# Node_MCU_Power_Shield.net
KiCad netlist of a schematic drawn in Altium Designer
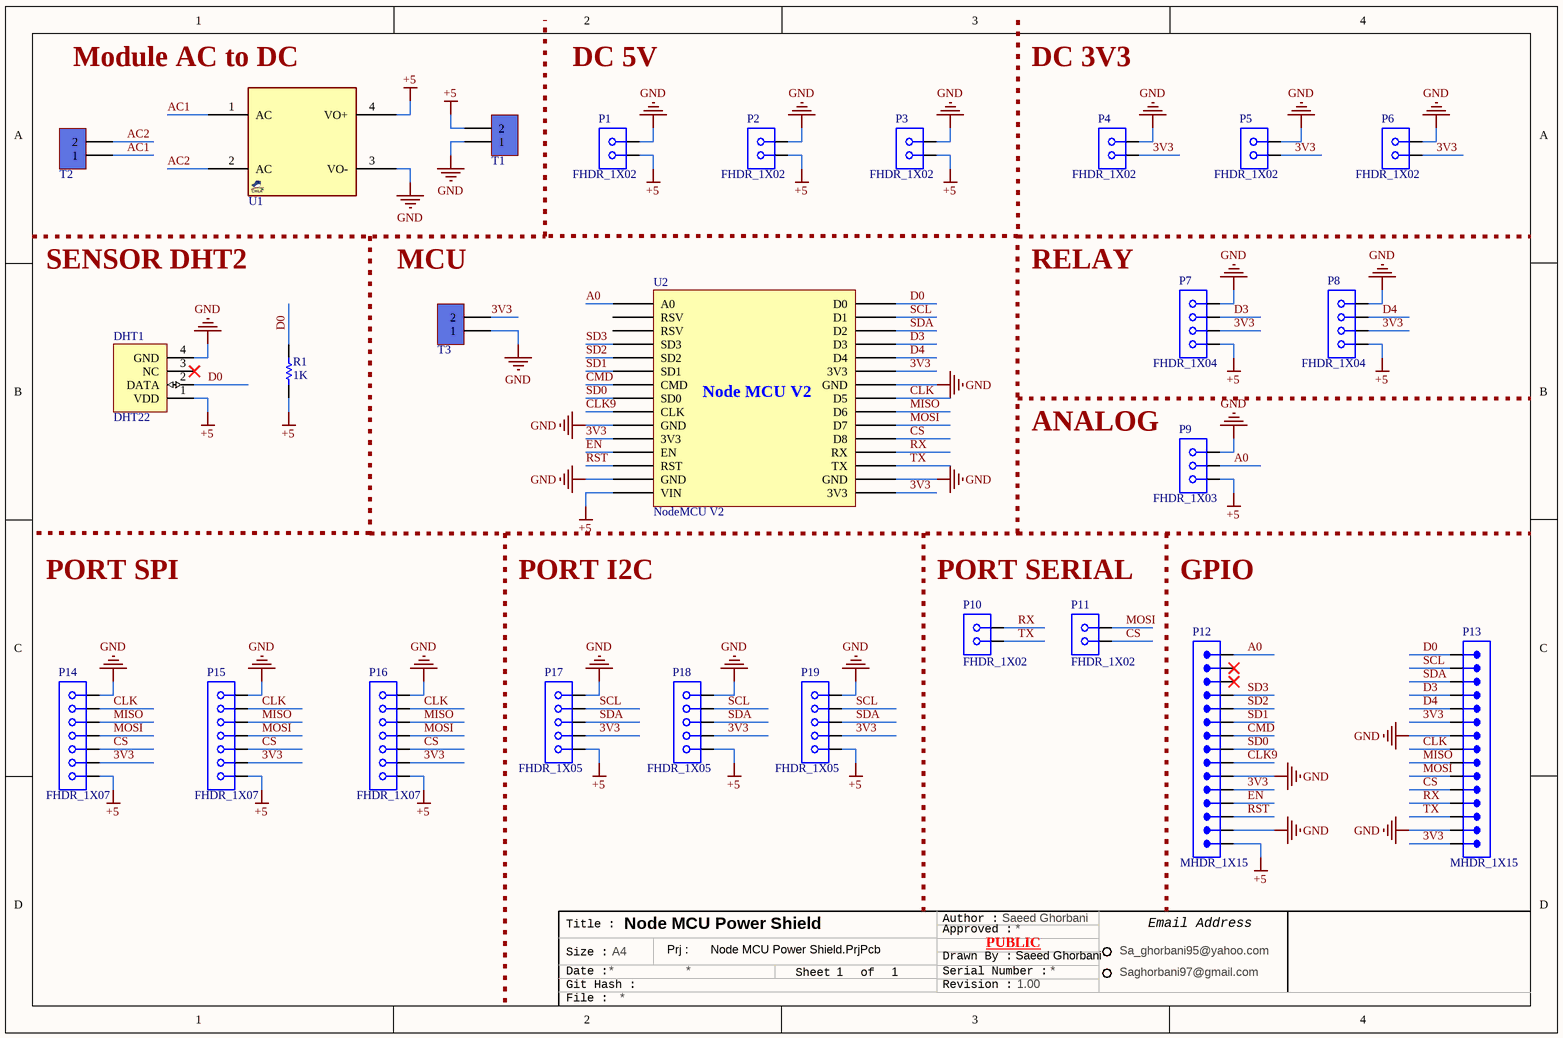
[diagram p0: Node MCU Power Shield.SchDoc]

(export (version "E")
  (design (tool "Eeschema 10.0.6"))
  (components
    (comp (ref "DHT1")
      (value "DHT22")
      (footprint "DHT22_THD")
      (description "Digital Humidity & Temprature Sensor")
      (libsource (lib "Altium") (part "DHT22"))
    )
    (comp (ref "P1")
      (value "FHDR_1X02")
      (footprint "FHDR1X02-254P")
      (description "Female Header 1X02")
      (libsource (lib "SJ Sockets & Connectors") (part "FHDR_1X02"))
    )
    (comp (ref "P2")
      (value "FHDR_1X02")
      (footprint "FHDR1X02-254P")
      (description "Female Header 1X02")
      (libsource (lib "SJ Sockets & Connectors") (part "FHDR_1X02"))
    )
    (comp (ref "P3")
      (value "FHDR_1X02")
      (footprint "FHDR1X02-254P")
      (description "Female Header 1X02")
      (libsource (lib "SJ Sockets & Connectors") (part "FHDR_1X02"))
    )
    (comp (ref "P4")
      (value "FHDR_1X02")
      (footprint "FHDR1X02-254P")
      (description "Female Header 1X02")
      (libsource (lib "SJ Sockets & Connectors") (part "FHDR_1X02"))
    )
    (comp (ref "P5")
      (value "FHDR_1X02")
      (footprint "FHDR1X02-254P")
      (description "Female Header 1X02")
      (libsource (lib "SJ Sockets & Connectors") (part "FHDR_1X02"))
    )
    (comp (ref "P6")
      (value "FHDR_1X02")
      (footprint "FHDR1X02-254P")
      (description "Female Header 1X02")
      (libsource (lib "SJ Sockets & Connectors") (part "FHDR_1X02"))
    )
    (comp (ref "P7")
      (value "FHDR_1X04")
      (footprint "FHDR1X04-254P")
      (description "Female Header 1X04")
      (libsource (lib "SJ Sockets & Connectors") (part "FHDR_1X04"))
    )
    (comp (ref "P8")
      (value "FHDR_1X04")
      (footprint "FHDR1X04-254P")
      (description "Female Header 1X04")
      (libsource (lib "SJ Sockets & Connectors") (part "FHDR_1X04"))
    )
    (comp (ref "P9")
      (value "FHDR_1X03")
      (footprint "FHDR1X03-254P")
      (description "Female Header 1X03")
      (libsource (lib "SJ Sockets & Connectors") (part "FHDR_1X03"))
    )
    (comp (ref "P10")
      (value "FHDR_1X02")
      (footprint "FHDR1X02-254P")
      (description "Female Header 1X02")
      (libsource (lib "SJ Sockets & Connectors") (part "FHDR_1X02"))
    )
    (comp (ref "P11")
      (value "FHDR_1X02")
      (footprint "FHDR1X02-254P")
      (description "Female Header 1X02")
      (libsource (lib "SJ Sockets & Connectors") (part "FHDR_1X02"))
    )
    (comp (ref "P12")
      (value "MHDR_1X15")
      (footprint "MHDR1X15-254P")
      (description "Male Header 1X15")
      (libsource (lib "SJ Sockets & Connectors") (part "MHDR_1X15"))
    )
    (comp (ref "P13")
      (value "MHDR_1X15")
      (footprint "MHDR1X15-254P")
      (description "Male Header 1X15")
      (libsource (lib "SJ Sockets & Connectors") (part "MHDR_1X15"))
    )
    (comp (ref "P14")
      (value "FHDR_1X07")
      (footprint "FHDR1X07-254P")
      (description "Female Header 1X07")
      (libsource (lib "SJ Sockets & Connectors") (part "FHDR_1X07"))
    )
    (comp (ref "P15")
      (value "FHDR_1X07")
      (footprint "FHDR1X07-254P")
      (description "Female Header 1X07")
      (libsource (lib "SJ Sockets & Connectors") (part "FHDR_1X07"))
    )
    (comp (ref "P16")
      (value "FHDR_1X07")
      (footprint "FHDR1X07-254P")
      (description "Female Header 1X07")
      (libsource (lib "SJ Sockets & Connectors") (part "FHDR_1X07"))
    )
    (comp (ref "P17")
      (value "FHDR_1X05")
      (footprint "FHDR1X05-254P")
      (description "Female Header 1X05")
      (libsource (lib "SJ Sockets & Connectors") (part "FHDR_1X05"))
    )
    (comp (ref "P18")
      (value "FHDR_1X05")
      (footprint "FHDR1X05-254P")
      (description "Female Header 1X05")
      (libsource (lib "SJ Sockets & Connectors") (part "FHDR_1X05"))
    )
    (comp (ref "P19")
      (value "FHDR_1X05")
      (footprint "FHDR1X05-254P")
      (description "Female Header 1X05")
      (libsource (lib "SJ Sockets & Connectors") (part "FHDR_1X05"))
    )
    (comp (ref "R1")
      (value "1K")
      (footprint "RES-(1/8)")
      (description "TOTAL DIP RESISTOR PACK")
      (fields (field (name "DESIGNER") "Ali Hafizi"))
      (libsource (lib "Altium") (part "RES DIP PACKAGE"))
    )
    (comp (ref "T1")
      (value "KF301_Terminal")
      (footprint "KF301 2PIN")
      (description "Terminal 2 Pin 250VAC 16A")
      (fields (field (name "DESIGNER") "Abbas Basereh"))
      (libsource (lib "") (part "KF301-2Pin_Terminal_1"))
    )
    (comp (ref "T2")
      (value "KF301_Terminal")
      (footprint "KF301 2PIN")
      (description "Terminal 2 Pin 250VAC 16A")
      (fields (field (name "DESIGNER") "Abbas Basereh"))
      (libsource (lib "Altium") (part "KF301-2Pin_Terminal"))
    )
    (comp (ref "T3")
      (value "KF301_Terminal")
      (footprint "KF301 2PIN")
      (description "Terminal 2 Pin 250VAC 16A")
      (fields (field (name "DESIGNER") "Abbas Basereh"))
      (libsource (lib "Altium") (part "KF301-2Pin_Terminal"))
    )
    (comp (ref "U1")
      (value "HLK-5M03")
      (footprint "HLK5M_4_38X23")
      (description "AC/DC CONVERTER")
      (fields (field (name "MANF") "HI-LINK"))
      (libsource (lib "module_ac2dc") (part "HLK-5M03"))
    )
    (comp (ref "U2")
      (value "NodeMCU V2")
      (footprint "NodeMCU V1.0 ESP-12E")
      (libsource (lib "NodeMCU") (part "NodeMCU V2"))
    )
  )
  (nets
    (net (code "1") (name "+5") (class "Default")
      (node (ref "DHT1") (pin "1") (pinfunction "VDD_1") (pintype "power_in"))
      (node (ref "P1") (pin "1") (pinfunction "1_1") (pintype "passive"))
      (node (ref "P12") (pin "1") (pinfunction "1_1") (pintype "passive"))
      (node (ref "P14") (pin "1") (pinfunction "1_1") (pintype "passive"))
      (node (ref "P15") (pin "1") (pinfunction "1_1") (pintype "passive"))
      (node (ref "P16") (pin "1") (pinfunction "1_1") (pintype "passive"))
      (node (ref "P17") (pin "1") (pinfunction "1_1") (pintype "passive"))
      (node (ref "P18") (pin "1") (pinfunction "1_1") (pintype "passive"))
      (node (ref "P19") (pin "1") (pinfunction "1_1") (pintype "passive"))
      (node (ref "P2") (pin "1") (pinfunction "1_1") (pintype "passive"))
      (node (ref "P3") (pin "1") (pinfunction "1_1") (pintype "passive"))
      (node (ref "P7") (pin "1") (pinfunction "1_1") (pintype "passive"))
      (node (ref "P8") (pin "1") (pinfunction "1_1") (pintype "passive"))
      (node (ref "P9") (pin "1") (pinfunction "1_1") (pintype "passive"))
      (node (ref "R1") (pin "1") (pinfunction "1_1") (pintype "passive"))
      (node (ref "T1") (pin "2") (pinfunction "2_2") (pintype "passive"))
      (node (ref "U1") (pin "4") (pinfunction "VO+_4") (pintype "power_in"))
      (node (ref "U2") (pin "15") (pinfunction "VIN_15") (pintype "passive"))
    )
    (net (code "2") (name "/3V3") (class "Default")
      (node (ref "P12") (pin "5") (pinfunction "5_5") (pintype "passive"))
      (node (ref "P13") (pin "15") (pinfunction "15_15") (pintype "passive"))
      (node (ref "P13") (pin "6") (pinfunction "6_6") (pintype "passive"))
      (node (ref "P14") (pin "2") (pinfunction "2_2") (pintype "passive"))
      (node (ref "P15") (pin "2") (pinfunction "2_2") (pintype "passive"))
      (node (ref "P16") (pin "2") (pinfunction "2_2") (pintype "passive"))
      (node (ref "P17") (pin "2") (pinfunction "2_2") (pintype "passive"))
      (node (ref "P18") (pin "2") (pinfunction "2_2") (pintype "passive"))
      (node (ref "P19") (pin "2") (pinfunction "2_2") (pintype "passive"))
      (node (ref "P4") (pin "1") (pinfunction "1_1") (pintype "passive"))
      (node (ref "P5") (pin "1") (pinfunction "1_1") (pintype "passive"))
      (node (ref "P6") (pin "1") (pinfunction "1_1") (pintype "passive"))
      (node (ref "P7") (pin "2") (pinfunction "2_2") (pintype "passive"))
      (node (ref "P8") (pin "2") (pinfunction "2_2") (pintype "passive"))
      (node (ref "T3") (pin "2") (pinfunction "2_2") (pintype "passive"))
      (node (ref "U2") (pin "11") (pinfunction "3V3_11") (pintype "passive"))
      (node (ref "U2") (pin "16") (pinfunction "3V3_16") (pintype "passive"))
      (node (ref "U2") (pin "25") (pinfunction "3V3_25") (pintype "passive"))
    )
    (net (code "3") (name "/A0") (class "Default")
      (node (ref "P12") (pin "15") (pinfunction "15_15") (pintype "passive"))
      (node (ref "P9") (pin "2") (pinfunction "2_2") (pintype "passive"))
      (node (ref "U2") (pin "1") (pinfunction "A0_1") (pintype "passive"))
    )
    (net (code "4") (name "/AC1") (class "Default")
      (node (ref "T2") (pin "1") (pinfunction "1_1") (pintype "passive"))
      (node (ref "U1") (pin "1") (pinfunction "AC_1") (pintype "power_in"))
    )
    (net (code "5") (name "/AC2") (class "Default")
      (node (ref "T2") (pin "2") (pinfunction "2_2") (pintype "passive"))
      (node (ref "U1") (pin "2") (pinfunction "AC_2") (pintype "power_in"))
    )
    (net (code "6") (name "/CLK") (class "Default")
      (node (ref "P13") (pin "8") (pinfunction "8_8") (pintype "passive"))
      (node (ref "P14") (pin "6") (pinfunction "6_6") (pintype "passive"))
      (node (ref "P15") (pin "6") (pinfunction "6_6") (pintype "passive"))
      (node (ref "P16") (pin "6") (pinfunction "6_6") (pintype "passive"))
      (node (ref "U2") (pin "23") (pinfunction "D5_23") (pintype "passive"))
    )
    (net (code "7") (name "/CLK9") (class "Default")
      (node (ref "P12") (pin "7") (pinfunction "7_7") (pintype "passive"))
      (node (ref "U2") (pin "9") (pinfunction "CLK_9") (pintype "passive"))
    )
    (net (code "8") (name "/CMD") (class "Default")
      (node (ref "P12") (pin "9") (pinfunction "9_9") (pintype "passive"))
      (node (ref "U2") (pin "7") (pinfunction "CMD_7") (pintype "passive"))
    )
    (net (code "9") (name "/CS") (class "Default")
      (node (ref "P11") (pin "1") (pinfunction "1_1") (pintype "passive"))
      (node (ref "P13") (pin "11") (pinfunction "11_11") (pintype "passive"))
      (node (ref "P14") (pin "3") (pinfunction "3_3") (pintype "passive"))
      (node (ref "P15") (pin "3") (pinfunction "3_3") (pintype "passive"))
      (node (ref "P16") (pin "3") (pinfunction "3_3") (pintype "passive"))
      (node (ref "U2") (pin "20") (pinfunction "D8_20") (pintype "passive"))
    )
    (net (code "10") (name "/D0") (class "Default")
      (node (ref "DHT1") (pin "2") (pinfunction "DATA_2") (pintype "bidirectional"))
      (node (ref "P13") (pin "1") (pinfunction "1_1") (pintype "passive"))
      (node (ref "R1") (pin "2") (pinfunction "2_2") (pintype "passive"))
      (node (ref "U2") (pin "30") (pinfunction "D0_30") (pintype "passive"))
    )
    (net (code "11") (name "/D3") (class "Default")
      (node (ref "P13") (pin "4") (pinfunction "4_4") (pintype "passive"))
      (node (ref "P7") (pin "3") (pinfunction "3_3") (pintype "passive"))
      (node (ref "U2") (pin "27") (pinfunction "D3_27") (pintype "passive"))
    )
    (net (code "12") (name "/D4") (class "Default")
      (node (ref "P13") (pin "5") (pinfunction "5_5") (pintype "passive"))
      (node (ref "P8") (pin "3") (pinfunction "3_3") (pintype "passive"))
      (node (ref "U2") (pin "26") (pinfunction "D4_26") (pintype "passive"))
    )
    (net (code "13") (name "/EN") (class "Default")
      (node (ref "P12") (pin "4") (pinfunction "4_4") (pintype "passive"))
      (node (ref "U2") (pin "12") (pinfunction "EN_12") (pintype "passive"))
    )
    (net (code "14") (name "/MISO") (class "Default")
      (node (ref "P13") (pin "9") (pinfunction "9_9") (pintype "passive"))
      (node (ref "P14") (pin "5") (pinfunction "5_5") (pintype "passive"))
      (node (ref "P15") (pin "5") (pinfunction "5_5") (pintype "passive"))
      (node (ref "P16") (pin "5") (pinfunction "5_5") (pintype "passive"))
      (node (ref "U2") (pin "22") (pinfunction "D6_22") (pintype "passive"))
    )
    (net (code "15") (name "/MOSI") (class "Default")
      (node (ref "P11") (pin "2") (pinfunction "2_2") (pintype "passive"))
      (node (ref "P13") (pin "10") (pinfunction "10_10") (pintype "passive"))
      (node (ref "P14") (pin "4") (pinfunction "4_4") (pintype "passive"))
      (node (ref "P15") (pin "4") (pinfunction "4_4") (pintype "passive"))
      (node (ref "P16") (pin "4") (pinfunction "4_4") (pintype "passive"))
      (node (ref "U2") (pin "21") (pinfunction "D7_21") (pintype "passive"))
    )
    (net (code "16") (name "/RST") (class "Default")
      (node (ref "P12") (pin "3") (pinfunction "3_3") (pintype "passive"))
      (node (ref "U2") (pin "13") (pinfunction "RST_13") (pintype "passive"))
    )
    (net (code "17") (name "/RX") (class "Default")
      (node (ref "P10") (pin "2") (pinfunction "2_2") (pintype "passive"))
      (node (ref "P13") (pin "12") (pinfunction "12_12") (pintype "passive"))
      (node (ref "U2") (pin "19") (pinfunction "RX_19") (pintype "passive"))
    )
    (net (code "18") (name "/SCL") (class "Default")
      (node (ref "P13") (pin "2") (pinfunction "2_2") (pintype "passive"))
      (node (ref "P17") (pin "4") (pinfunction "4_4") (pintype "passive"))
      (node (ref "P18") (pin "4") (pinfunction "4_4") (pintype "passive"))
      (node (ref "P19") (pin "4") (pinfunction "4_4") (pintype "passive"))
      (node (ref "U2") (pin "29") (pinfunction "D1_29") (pintype "passive"))
    )
    (net (code "19") (name "/SD0") (class "Default")
      (node (ref "P12") (pin "8") (pinfunction "8_8") (pintype "passive"))
      (node (ref "U2") (pin "8") (pinfunction "SD0_8") (pintype "passive"))
    )
    (net (code "20") (name "/SD1") (class "Default")
      (node (ref "P12") (pin "10") (pinfunction "10_10") (pintype "passive"))
      (node (ref "U2") (pin "6") (pinfunction "SD1_6") (pintype "passive"))
    )
    (net (code "21") (name "/SD2") (class "Default")
      (node (ref "P12") (pin "11") (pinfunction "11_11") (pintype "passive"))
      (node (ref "U2") (pin "5") (pinfunction "SD2_5") (pintype "passive"))
    )
    (net (code "22") (name "/SD3") (class "Default")
      (node (ref "P12") (pin "12") (pinfunction "12_12") (pintype "passive"))
      (node (ref "U2") (pin "4") (pinfunction "SD3_4") (pintype "passive"))
    )
    (net (code "23") (name "/SDA") (class "Default")
      (node (ref "P13") (pin "3") (pinfunction "3_3") (pintype "passive"))
      (node (ref "P17") (pin "3") (pinfunction "3_3") (pintype "passive"))
      (node (ref "P18") (pin "3") (pinfunction "3_3") (pintype "passive"))
      (node (ref "P19") (pin "3") (pinfunction "3_3") (pintype "passive"))
      (node (ref "U2") (pin "28") (pinfunction "D2_28") (pintype "passive"))
    )
    (net (code "24") (name "/TX") (class "Default")
      (node (ref "P10") (pin "1") (pinfunction "1_1") (pintype "passive"))
      (node (ref "P13") (pin "13") (pinfunction "13_13") (pintype "passive"))
      (node (ref "U2") (pin "18") (pinfunction "TX_18") (pintype "passive"))
    )
    (net (code "25") (name "GND") (class "Default")
      (node (ref "DHT1") (pin "4") (pinfunction "GND_4") (pintype "power_in"))
      (node (ref "P1") (pin "2") (pinfunction "2_2") (pintype "passive"))
      (node (ref "P12") (pin "2") (pinfunction "2_2") (pintype "passive"))
      (node (ref "P12") (pin "6") (pinfunction "6_6") (pintype "passive"))
      (node (ref "P13") (pin "14") (pinfunction "14_14") (pintype "passive"))
      (node (ref "P13") (pin "7") (pinfunction "7_7") (pintype "passive"))
      (node (ref "P14") (pin "7") (pinfunction "7_7") (pintype "passive"))
      (node (ref "P15") (pin "7") (pinfunction "7_7") (pintype "passive"))
      (node (ref "P16") (pin "7") (pinfunction "7_7") (pintype "passive"))
      (node (ref "P17") (pin "5") (pinfunction "5_5") (pintype "passive"))
      (node (ref "P18") (pin "5") (pinfunction "5_5") (pintype "passive"))
      (node (ref "P19") (pin "5") (pinfunction "5_5") (pintype "passive"))
      (node (ref "P2") (pin "2") (pinfunction "2_2") (pintype "passive"))
      (node (ref "P3") (pin "2") (pinfunction "2_2") (pintype "passive"))
      (node (ref "P4") (pin "2") (pinfunction "2_2") (pintype "passive"))
      (node (ref "P5") (pin "2") (pinfunction "2_2") (pintype "passive"))
      (node (ref "P6") (pin "2") (pinfunction "2_2") (pintype "passive"))
      (node (ref "P7") (pin "4") (pinfunction "4_4") (pintype "passive"))
      (node (ref "P8") (pin "4") (pinfunction "4_4") (pintype "passive"))
      (node (ref "P9") (pin "3") (pinfunction "3_3") (pintype "passive"))
      (node (ref "T1") (pin "1") (pinfunction "1_1") (pintype "passive"))
      (node (ref "T3") (pin "1") (pinfunction "1_1") (pintype "passive"))
      (node (ref "U1") (pin "3") (pinfunction "VO-_3") (pintype "power_in"))
      (node (ref "U2") (pin "10") (pinfunction "GND_10") (pintype "passive"))
      (node (ref "U2") (pin "14") (pinfunction "GND_14") (pintype "passive"))
      (node (ref "U2") (pin "17") (pinfunction "GND_17") (pintype "passive"))
      (node (ref "U2") (pin "24") (pinfunction "GND_24") (pintype "passive"))
    )
    (net (code "26") (name "unconnected-(DHT1-NC-Pad3)") (class "Default")
      (node (ref "DHT1") (pin "3") (pinfunction "NC_3") (pintype "passive+no_connect"))
    )
    (net (code "27") (name "unconnected-(P12-Pad13)") (class "Default")
      (node (ref "P12") (pin "13") (pinfunction "13_13") (pintype "passive+no_connect"))
    )
    (net (code "28") (name "unconnected-(P12-Pad14)") (class "Default")
      (node (ref "P12") (pin "14") (pinfunction "14_14") (pintype "passive+no_connect"))
    )
    (net (code "29") (name "unconnected-(U2-RSV-Pad2)") (class "Default")
      (node (ref "U2") (pin "2") (pinfunction "RSV_2") (pintype "passive"))
    )
    (net (code "30") (name "unconnected-(U2-RSV-Pad3)") (class "Default")
      (node (ref "U2") (pin "3") (pinfunction "RSV_3") (pintype "passive"))
    )
  )
)
